# PFC_v1.net
KiCad netlist of a schematic drawn in EAGLE
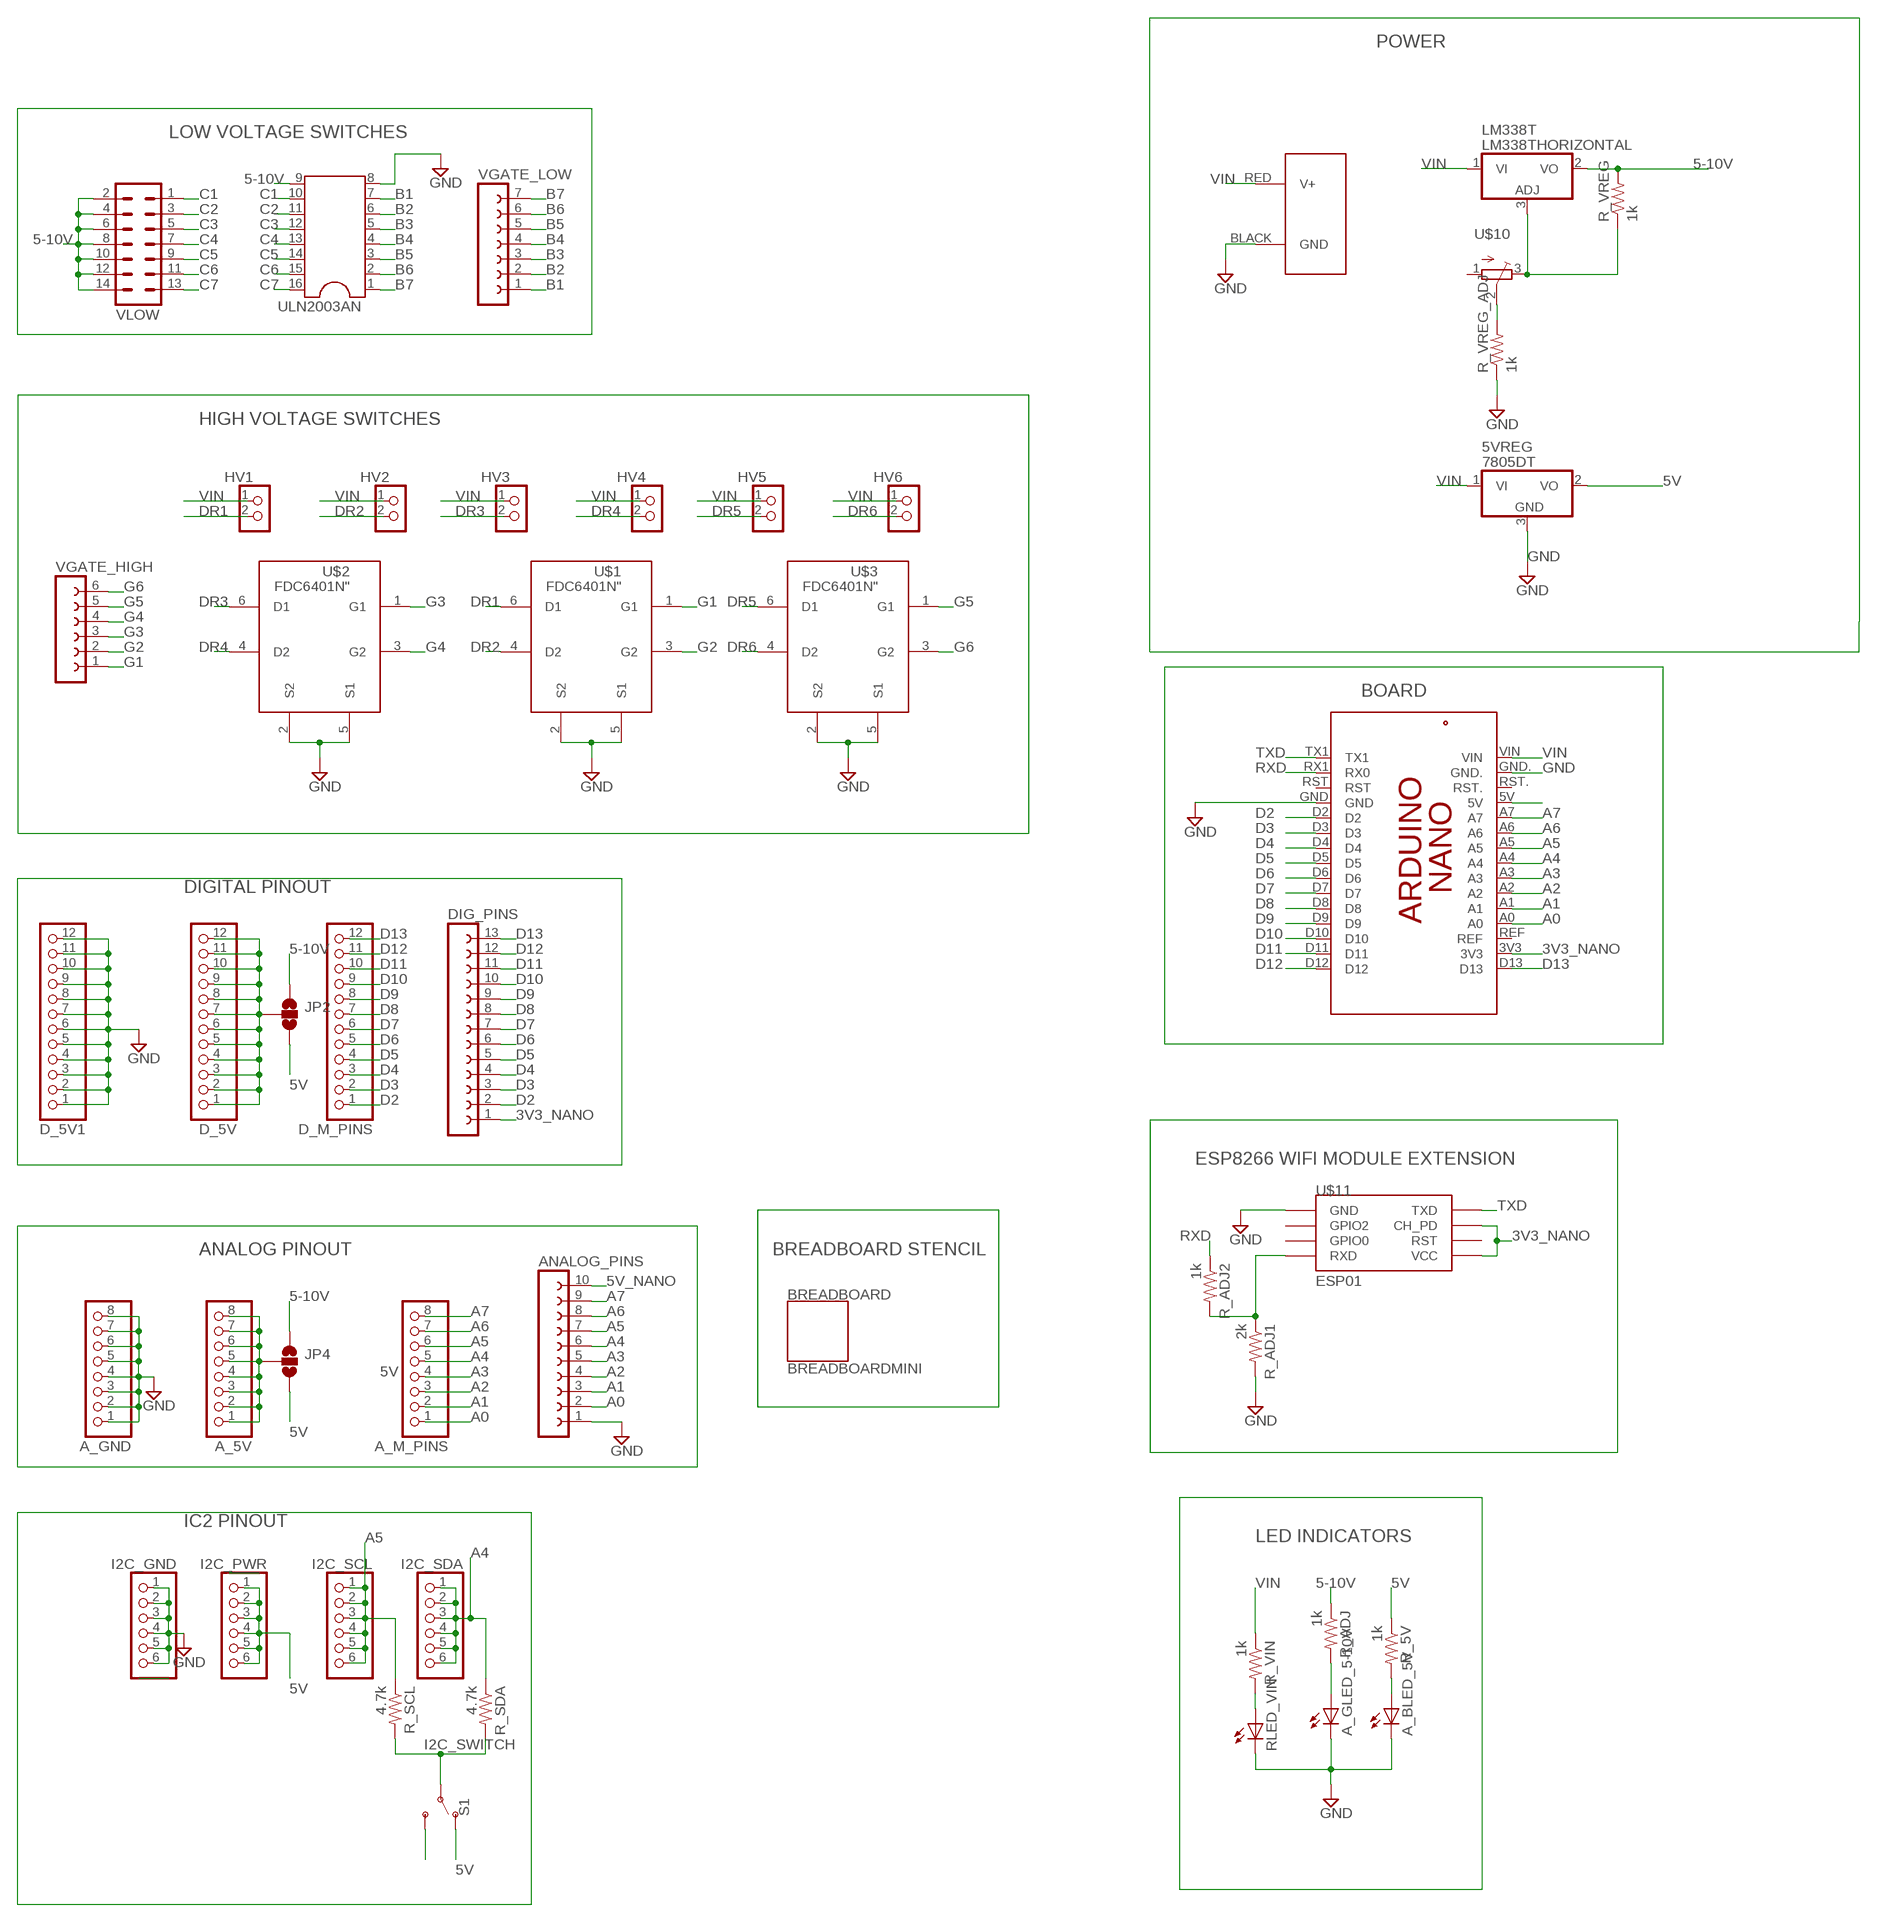
[diagram p0: schematic, sheet 1]

(export (version "E")
  (design (tool "Eeschema 10.0.6"))
  (components
    (comp (ref "5VREG")
      (value "7805DT")
      (footprint "eagle-import:TO252")
      (libsource (lib "eagle-import") (part "78DT05"))
    )
    (comp (ref "ANALOG_PINS")
      (value "FE10-1")
      (footprint "eagle-import:FE10")
      (libsource (lib "eagle-import") (part "FE10-1"))
    )
    (comp (ref "A_5V")
      (value "PINHD-1X8CLEANBIG")
      (footprint "eagle-import:1X08-CLEANBIG")
      (libsource (lib "eagle-import") (part "PINHD-1X8CLEANBIG"))
    )
    (comp (ref "A_BLED_5V")
      (value "LEDCHIP-LED0603")
      (footprint "eagle-import:CHIP-LED0603")
      (libsource (lib "eagle-import") (part "LEDCHIP-LED0603"))
    )
    (comp (ref "A_GLED_5-10V")
      (value "LEDCHIP-LED0603")
      (footprint "eagle-import:CHIP-LED0603")
      (libsource (lib "eagle-import") (part "LEDCHIP-LED0603"))
    )
    (comp (ref "A_GND")
      (value "PINHD-1X8CLEANBIG")
      (footprint "eagle-import:1X08-CLEANBIG")
      (libsource (lib "eagle-import") (part "PINHD-1X8CLEANBIG"))
    )
    (comp (ref "A_M_PINS")
      (value "PINHD-1X8CLEANBIG")
      (footprint "eagle-import:1X08-CLEANBIG")
      (libsource (lib "eagle-import") (part "PINHD-1X8CLEANBIG"))
    )
    (comp (ref "BREADBOARD")
      (value "BREADBOARDMINI")
      (footprint "eagle-import:BREADBOARD-MINI")
      (libsource (lib "eagle-import") (part "BREADBOARDMINI"))
    )
    (comp (ref "DIG_PINS")
      (value "FE13-1")
      (footprint "eagle-import:FE13")
      (libsource (lib "eagle-import") (part "FE13-1"))
    )
    (comp (ref "D_5V")
      (value "PINHD-1X12-CB")
      (footprint "eagle-import:1X12-CB")
      (libsource (lib "eagle-import") (part "PINHD-1X12-CB"))
    )
    (comp (ref "D_5V1")
      (value "PINHD-1X12-CB")
      (footprint "eagle-import:1X12-CB")
      (libsource (lib "eagle-import") (part "PINHD-1X12-CB"))
    )
    (comp (ref "D_M_PINS")
      (value "PINHD-1X12-CB")
      (footprint "eagle-import:1X12-CB")
      (libsource (lib "eagle-import") (part "PINHD-1X12-CB"))
    )
    (comp (ref "HV1")
      (value "PINHD-2X1")
      (footprint "eagle-import:2X01")
      (libsource (lib "eagle-import") (part "PINHD-2X1"))
    )
    (comp (ref "HV2")
      (value "PINHD-2X1")
      (footprint "eagle-import:2X01")
      (libsource (lib "eagle-import") (part "PINHD-2X1"))
    )
    (comp (ref "HV3")
      (value "PINHD-2X1")
      (footprint "eagle-import:2X01")
      (libsource (lib "eagle-import") (part "PINHD-2X1"))
    )
    (comp (ref "HV4")
      (value "PINHD-2X1")
      (footprint "eagle-import:2X01")
      (libsource (lib "eagle-import") (part "PINHD-2X1"))
    )
    (comp (ref "HV5")
      (value "PINHD-2X1")
      (footprint "eagle-import:2X01")
      (libsource (lib "eagle-import") (part "PINHD-2X1"))
    )
    (comp (ref "HV6")
      (value "PINHD-2X1")
      (footprint "eagle-import:2X01")
      (libsource (lib "eagle-import") (part "PINHD-2X1"))
    )
    (comp (ref "I2C_GND")
      (value "PINHD-1X6CLEAN")
      (footprint "eagle-import:1X06-CLEAN")
      (libsource (lib "eagle-import") (part "PINHD-1X6CLEAN"))
    )
    (comp (ref "I2C_PWR")
      (value "PINHD-1X6CLEAN")
      (footprint "eagle-import:1X06-CLEAN")
      (libsource (lib "eagle-import") (part "PINHD-1X6CLEAN"))
    )
    (comp (ref "I2C_SCL")
      (value "PINHD-1X6CLEAN")
      (footprint "eagle-import:1X06-CLEAN")
      (libsource (lib "eagle-import") (part "PINHD-1X6CLEAN"))
    )
    (comp (ref "I2C_SDA")
      (value "PINHD-1X6CLEAN")
      (footprint "eagle-import:1X06-CLEAN")
      (libsource (lib "eagle-import") (part "PINHD-1X6CLEAN"))
    )
    (comp (ref "J1")
      (value "POWERPOLE_POWER25A_HORIZONTAL_G2")
      (footprint "eagle-import:POWERPOLE_PAIR_25A_HORIZ_G2")
      (libsource (lib "eagle-import") (part "POWERPOLE_POWER25A_HORIZONTAL_G2"))
    )
    (comp (ref "JP2")
      (value "SOLDERJUMPER_2WAYT")
      (footprint "eagle-import:SJ_2")
      (libsource (lib "eagle-import") (part "SOLDERJUMPER_2WAYT"))
    )
    (comp (ref "JP4")
      (value "SOLDERJUMPER_2WAYT")
      (footprint "eagle-import:SJ_2")
      (libsource (lib "eagle-import") (part "SOLDERJUMPER_2WAYT"))
    )
    (comp (ref "LM338T")
      (value "LM338THORIZONTAL")
      (footprint "eagle-import:TO220H")
      (libsource (lib "eagle-import") (part "LM338THORIZONTAL"))
    )
    (comp (ref "PCB1")
      (value "ARDUINO_NANO_SHIELD")
      (footprint "eagle-import:ARDUINO_NANO_SHIELD")
      (libsource (lib "eagle-import") (part "ARDUINO_NANO_SHIELD"))
    )
    (comp (ref "RLED_VIN")
      (value "LEDCHIP-LED0603")
      (footprint "eagle-import:CHIP-LED0603")
      (libsource (lib "eagle-import") (part "LEDCHIP-LED0603"))
    )
    (comp (ref "R_5V")
      (value "1k")
      (footprint "eagle-import:R0603")
      (libsource (lib "eagle-import") (part "R-US_R0603"))
    )
    (comp (ref "R_ADJ")
      (value "1k")
      (footprint "eagle-import:R0603")
      (libsource (lib "eagle-import") (part "R-US_R0603"))
    )
    (comp (ref "R_ADJ1")
      (value "2k")
      (footprint "eagle-import:R0603")
      (libsource (lib "eagle-import") (part "R-US_R0603"))
    )
    (comp (ref "R_ADJ2")
      (value "1k")
      (footprint "eagle-import:R0603")
      (libsource (lib "eagle-import") (part "R-US_R0603"))
    )
    (comp (ref "R_SCL")
      (value "4.7k")
      (footprint "eagle-import:R0603")
      (libsource (lib "eagle-import") (part "R-US_R0603"))
    )
    (comp (ref "R_SDA")
      (value "4.7k")
      (footprint "eagle-import:R0603")
      (libsource (lib "eagle-import") (part "R-US_R0603"))
    )
    (comp (ref "R_VIN")
      (value "1k")
      (footprint "eagle-import:R0603")
      (libsource (lib "eagle-import") (part "R-US_R0603"))
    )
    (comp (ref "R_VREG")
      (value "1k")
      (footprint "eagle-import:R0603")
      (libsource (lib "eagle-import") (part "R-US_R0603"))
    )
    (comp (ref "R_VREG_ADJ")
      (value "1k")
      (footprint "eagle-import:R0603")
      (libsource (lib "eagle-import") (part "R-US_R0603"))
    )
    (comp (ref "S1")
      (value "SWITCH-SPDT-PTH-11.6X4.0MM")
      (footprint "eagle-import:SWITCH_SPDT_PTH_11.6X4.0MM")
      (libsource (lib "eagle-import") (part "SWITCH-SPDT-PTH-11.6X4.0MM"))
    )
    (comp (ref "U$1")
      (value "FDC6401N\"")
      (footprint "eagle-import:SSOT-6")
      (libsource (lib "eagle-import") (part "FDC6401N{dblquote}"))
    )
    (comp (ref "U$2")
      (value "FDC6401N\"")
      (footprint "eagle-import:SSOT-6")
      (libsource (lib "eagle-import") (part "FDC6401N{dblquote}"))
    )
    (comp (ref "U$3")
      (value "FDC6401N\"")
      (footprint "eagle-import:SSOT-6")
      (libsource (lib "eagle-import") (part "FDC6401N{dblquote}"))
    )
    (comp (ref "U$10")
      (value "TRIMPOTTC33X")
      (footprint "eagle-import:TC33X")
      (libsource (lib "eagle-import") (part "TRIMPOTTC33X"))
    )
    (comp (ref "U$11")
      (value "ESP01")
      (footprint "eagle-import:ESP01")
      (libsource (lib "eagle-import") (part "ESP01"))
    )
    (comp (ref "ULN2003AN")
      (value "DIL16S")
      (footprint "eagle-import:SOCKET-16")
      (libsource (lib "eagle-import") (part "DIL16S"))
    )
    (comp (ref "VGATE_HIGH")
      (value "FE06-1")
      (footprint "eagle-import:FE06")
      (libsource (lib "eagle-import") (part "FE06-1"))
    )
    (comp (ref "VGATE_LOW")
      (value "FE07-1")
      (footprint "eagle-import:FE07")
      (libsource (lib "eagle-import") (part "FE07-1"))
    )
    (comp (ref "VLOW")
      (value "MA07-2")
      (footprint "eagle-import:MA07-2")
      (libsource (lib "eagle-import") (part "MA07-2"))
    )
  )
  (nets
    (net (code "1") (name "/3V3_NANO") (class "Default")
      (node (ref "DIG_PINS") (pin "1") (pinfunction "1_1") (pintype "passive"))
      (node (ref "PCB1") (pin "3V3") (pinfunction "3V3_3V3") (pintype "bidirectional"))
      (node (ref "U$11") (pin "CH_PD") (pinfunction "CH_PD_CH_PD") (pintype "bidirectional"))
      (node (ref "U$11") (pin "VCC") (pinfunction "VCC_VCC") (pintype "bidirectional"))
    )
    (net (code "2") (name "/5-10V") (class "Default")
      (node (ref "JP2") (pin "1") (pinfunction "1_1") (pintype "passive"))
      (node (ref "JP4") (pin "1") (pinfunction "1_1") (pintype "passive"))
      (node (ref "LM338T") (pin "2") (pinfunction "VO_2") (pintype "passive"))
      (node (ref "R_ADJ") (pin "1") (pinfunction "1_1") (pintype "passive"))
      (node (ref "R_VREG") (pin "2") (pinfunction "2_2") (pintype "passive"))
      (node (ref "ULN2003AN") (pin "9") (pinfunction "9_9") (pintype "passive"))
      (node (ref "VLOW") (pin "10") (pinfunction "10_10") (pintype "passive"))
      (node (ref "VLOW") (pin "12") (pinfunction "12_12") (pintype "passive"))
      (node (ref "VLOW") (pin "14") (pinfunction "14_14") (pintype "passive"))
      (node (ref "VLOW") (pin "2") (pinfunction "2_2") (pintype "passive"))
      (node (ref "VLOW") (pin "4") (pinfunction "4_4") (pintype "passive"))
      (node (ref "VLOW") (pin "6") (pinfunction "6_6") (pintype "passive"))
      (node (ref "VLOW") (pin "8") (pinfunction "8_8") (pintype "passive"))
    )
    (net (code "3") (name "/5V") (class "Default")
      (node (ref "5VREG") (pin "2") (pinfunction "VO_2") (pintype "passive"))
      (node (ref "I2C_PWR") (pin "1") (pinfunction "1_1") (pintype "passive"))
      (node (ref "I2C_PWR") (pin "2") (pinfunction "2_2") (pintype "passive"))
      (node (ref "I2C_PWR") (pin "3") (pinfunction "3_3") (pintype "passive"))
      (node (ref "I2C_PWR") (pin "4") (pinfunction "4_4") (pintype "passive"))
      (node (ref "I2C_PWR") (pin "5") (pinfunction "5_5") (pintype "passive"))
      (node (ref "I2C_PWR") (pin "6") (pinfunction "6_6") (pintype "passive"))
      (node (ref "JP2") (pin "3") (pinfunction "3_3") (pintype "passive"))
      (node (ref "JP4") (pin "3") (pinfunction "3_3") (pintype "passive"))
      (node (ref "R_5V") (pin "1") (pinfunction "1_1") (pintype "passive"))
      (node (ref "S1") (pin "1") (pinfunction "O_1") (pintype "passive"))
    )
    (net (code "4") (name "/5V_NANO") (class "Default")
      (node (ref "ANALOG_PINS") (pin "10") (pinfunction "10_10") (pintype "passive"))
      (node (ref "PCB1") (pin "5V") (pinfunction "5V_5V") (pintype "bidirectional"))
    )
    (net (code "5") (name "/A0") (class "Default")
      (node (ref "ANALOG_PINS") (pin "2") (pinfunction "2_2") (pintype "passive"))
      (node (ref "A_M_PINS") (pin "1") (pinfunction "1_1") (pintype "passive"))
      (node (ref "PCB1") (pin "A0") (pinfunction "A0_A0") (pintype "bidirectional"))
    )
    (net (code "6") (name "/A1") (class "Default")
      (node (ref "ANALOG_PINS") (pin "3") (pinfunction "3_3") (pintype "passive"))
      (node (ref "A_M_PINS") (pin "2") (pinfunction "2_2") (pintype "passive"))
      (node (ref "PCB1") (pin "A1") (pinfunction "A1_A1") (pintype "bidirectional"))
    )
    (net (code "7") (name "/A2") (class "Default")
      (node (ref "ANALOG_PINS") (pin "4") (pinfunction "4_4") (pintype "passive"))
      (node (ref "A_M_PINS") (pin "3") (pinfunction "3_3") (pintype "passive"))
      (node (ref "PCB1") (pin "A2") (pinfunction "A2_A2") (pintype "bidirectional"))
    )
    (net (code "8") (name "/A3") (class "Default")
      (node (ref "ANALOG_PINS") (pin "5") (pinfunction "5_5") (pintype "passive"))
      (node (ref "A_M_PINS") (pin "4") (pinfunction "4_4") (pintype "passive"))
      (node (ref "PCB1") (pin "A3") (pinfunction "A3_A3") (pintype "bidirectional"))
    )
    (net (code "9") (name "/A4") (class "Default")
      (node (ref "ANALOG_PINS") (pin "6") (pinfunction "6_6") (pintype "passive"))
      (node (ref "A_M_PINS") (pin "5") (pinfunction "5_5") (pintype "passive"))
      (node (ref "I2C_SDA") (pin "1") (pinfunction "1_1") (pintype "passive"))
      (node (ref "I2C_SDA") (pin "2") (pinfunction "2_2") (pintype "passive"))
      (node (ref "I2C_SDA") (pin "3") (pinfunction "3_3") (pintype "passive"))
      (node (ref "I2C_SDA") (pin "4") (pinfunction "4_4") (pintype "passive"))
      (node (ref "I2C_SDA") (pin "5") (pinfunction "5_5") (pintype "passive"))
      (node (ref "I2C_SDA") (pin "6") (pinfunction "6_6") (pintype "passive"))
      (node (ref "PCB1") (pin "A4") (pinfunction "A4_A4") (pintype "bidirectional"))
      (node (ref "R_SDA") (pin "1") (pinfunction "1_1") (pintype "passive"))
    )
    (net (code "10") (name "/A5") (class "Default")
      (node (ref "ANALOG_PINS") (pin "7") (pinfunction "7_7") (pintype "passive"))
      (node (ref "A_M_PINS") (pin "6") (pinfunction "6_6") (pintype "passive"))
      (node (ref "I2C_SCL") (pin "1") (pinfunction "1_1") (pintype "passive"))
      (node (ref "I2C_SCL") (pin "2") (pinfunction "2_2") (pintype "passive"))
      (node (ref "I2C_SCL") (pin "3") (pinfunction "3_3") (pintype "passive"))
      (node (ref "I2C_SCL") (pin "4") (pinfunction "4_4") (pintype "passive"))
      (node (ref "I2C_SCL") (pin "5") (pinfunction "5_5") (pintype "passive"))
      (node (ref "I2C_SCL") (pin "6") (pinfunction "6_6") (pintype "passive"))
      (node (ref "PCB1") (pin "A5") (pinfunction "A5_A5") (pintype "bidirectional"))
      (node (ref "R_SCL") (pin "1") (pinfunction "1_1") (pintype "passive"))
    )
    (net (code "11") (name "/A6") (class "Default")
      (node (ref "ANALOG_PINS") (pin "8") (pinfunction "8_8") (pintype "passive"))
      (node (ref "A_M_PINS") (pin "7") (pinfunction "7_7") (pintype "passive"))
      (node (ref "PCB1") (pin "A6") (pinfunction "A6_A6") (pintype "bidirectional"))
    )
    (net (code "12") (name "/A7") (class "Default")
      (node (ref "ANALOG_PINS") (pin "9") (pinfunction "9_9") (pintype "passive"))
      (node (ref "A_M_PINS") (pin "8") (pinfunction "8_8") (pintype "passive"))
      (node (ref "PCB1") (pin "A7") (pinfunction "A7_A7") (pintype "bidirectional"))
    )
    (net (code "13") (name "/B1") (class "Default")
      (node (ref "ULN2003AN") (pin "7") (pinfunction "7_7") (pintype "passive"))
      (node (ref "VGATE_LOW") (pin "1") (pinfunction "1_1") (pintype "passive"))
    )
    (net (code "14") (name "/B2") (class "Default")
      (node (ref "ULN2003AN") (pin "6") (pinfunction "6_6") (pintype "passive"))
      (node (ref "VGATE_LOW") (pin "2") (pinfunction "2_2") (pintype "passive"))
    )
    (net (code "15") (name "/B3") (class "Default")
      (node (ref "ULN2003AN") (pin "5") (pinfunction "5_5") (pintype "passive"))
      (node (ref "VGATE_LOW") (pin "3") (pinfunction "3_3") (pintype "passive"))
    )
    (net (code "16") (name "/B4") (class "Default")
      (node (ref "ULN2003AN") (pin "4") (pinfunction "4_4") (pintype "passive"))
      (node (ref "VGATE_LOW") (pin "4") (pinfunction "4_4") (pintype "passive"))
    )
    (net (code "17") (name "/B5") (class "Default")
      (node (ref "ULN2003AN") (pin "3") (pinfunction "3_3") (pintype "passive"))
      (node (ref "VGATE_LOW") (pin "5") (pinfunction "5_5") (pintype "passive"))
    )
    (net (code "18") (name "/B6") (class "Default")
      (node (ref "ULN2003AN") (pin "2") (pinfunction "2_2") (pintype "passive"))
      (node (ref "VGATE_LOW") (pin "6") (pinfunction "6_6") (pintype "passive"))
    )
    (net (code "19") (name "/B7") (class "Default")
      (node (ref "ULN2003AN") (pin "1") (pinfunction "1_1") (pintype "passive"))
      (node (ref "VGATE_LOW") (pin "7") (pinfunction "7_7") (pintype "passive"))
    )
    (net (code "20") (name "/C1") (class "Default")
      (node (ref "ULN2003AN") (pin "10") (pinfunction "10_10") (pintype "passive"))
      (node (ref "VLOW") (pin "1") (pinfunction "1_1") (pintype "passive"))
    )
    (net (code "21") (name "/C2") (class "Default")
      (node (ref "ULN2003AN") (pin "11") (pinfunction "11_11") (pintype "passive"))
      (node (ref "VLOW") (pin "3") (pinfunction "3_3") (pintype "passive"))
    )
    (net (code "22") (name "/C3") (class "Default")
      (node (ref "ULN2003AN") (pin "12") (pinfunction "12_12") (pintype "passive"))
      (node (ref "VLOW") (pin "5") (pinfunction "5_5") (pintype "passive"))
    )
    (net (code "23") (name "/C4") (class "Default")
      (node (ref "ULN2003AN") (pin "13") (pinfunction "13_13") (pintype "passive"))
      (node (ref "VLOW") (pin "7") (pinfunction "7_7") (pintype "passive"))
    )
    (net (code "24") (name "/C5") (class "Default")
      (node (ref "ULN2003AN") (pin "14") (pinfunction "14_14") (pintype "passive"))
      (node (ref "VLOW") (pin "9") (pinfunction "9_9") (pintype "passive"))
    )
    (net (code "25") (name "/C6") (class "Default")
      (node (ref "ULN2003AN") (pin "15") (pinfunction "15_15") (pintype "passive"))
      (node (ref "VLOW") (pin "11") (pinfunction "11_11") (pintype "passive"))
    )
    (net (code "26") (name "/C7") (class "Default")
      (node (ref "ULN2003AN") (pin "16") (pinfunction "16_16") (pintype "passive"))
      (node (ref "VLOW") (pin "13") (pinfunction "13_13") (pintype "passive"))
    )
    (net (code "27") (name "/D2") (class "Default")
      (node (ref "DIG_PINS") (pin "2") (pinfunction "2_2") (pintype "passive"))
      (node (ref "D_M_PINS") (pin "1") (pinfunction "1_1") (pintype "passive"))
      (node (ref "PCB1") (pin "D2") (pinfunction "D2_D2") (pintype "bidirectional"))
    )
    (net (code "28") (name "/D3") (class "Default")
      (node (ref "DIG_PINS") (pin "3") (pinfunction "3_3") (pintype "passive"))
      (node (ref "D_M_PINS") (pin "2") (pinfunction "2_2") (pintype "passive"))
      (node (ref "PCB1") (pin "D3") (pinfunction "D3_D3") (pintype "bidirectional"))
    )
    (net (code "29") (name "/D4") (class "Default")
      (node (ref "DIG_PINS") (pin "4") (pinfunction "4_4") (pintype "passive"))
      (node (ref "D_M_PINS") (pin "3") (pinfunction "3_3") (pintype "passive"))
      (node (ref "PCB1") (pin "D4") (pinfunction "D4_D4") (pintype "bidirectional"))
    )
    (net (code "30") (name "/D5") (class "Default")
      (node (ref "DIG_PINS") (pin "5") (pinfunction "5_5") (pintype "passive"))
      (node (ref "D_M_PINS") (pin "4") (pinfunction "4_4") (pintype "passive"))
      (node (ref "PCB1") (pin "D5") (pinfunction "D5_D5") (pintype "bidirectional"))
    )
    (net (code "31") (name "/D6") (class "Default")
      (node (ref "DIG_PINS") (pin "6") (pinfunction "6_6") (pintype "passive"))
      (node (ref "D_M_PINS") (pin "5") (pinfunction "5_5") (pintype "passive"))
      (node (ref "PCB1") (pin "D6") (pinfunction "D6_D6") (pintype "bidirectional"))
    )
    (net (code "32") (name "/D7") (class "Default")
      (node (ref "DIG_PINS") (pin "7") (pinfunction "7_7") (pintype "passive"))
      (node (ref "D_M_PINS") (pin "6") (pinfunction "6_6") (pintype "passive"))
      (node (ref "PCB1") (pin "D7") (pinfunction "D7_D7") (pintype "bidirectional"))
    )
    (net (code "33") (name "/D8") (class "Default")
      (node (ref "DIG_PINS") (pin "8") (pinfunction "8_8") (pintype "passive"))
      (node (ref "D_M_PINS") (pin "7") (pinfunction "7_7") (pintype "passive"))
      (node (ref "PCB1") (pin "D8") (pinfunction "D8_D8") (pintype "bidirectional"))
    )
    (net (code "34") (name "/D9") (class "Default")
      (node (ref "DIG_PINS") (pin "9") (pinfunction "9_9") (pintype "passive"))
      (node (ref "D_M_PINS") (pin "8") (pinfunction "8_8") (pintype "passive"))
      (node (ref "PCB1") (pin "D9") (pinfunction "D9_D9") (pintype "bidirectional"))
    )
    (net (code "35") (name "/D10") (class "Default")
      (node (ref "DIG_PINS") (pin "10") (pinfunction "10_10") (pintype "passive"))
      (node (ref "D_M_PINS") (pin "9") (pinfunction "9_9") (pintype "passive"))
      (node (ref "PCB1") (pin "D10") (pinfunction "D10_D10") (pintype "bidirectional"))
    )
    (net (code "36") (name "/D11") (class "Default")
      (node (ref "DIG_PINS") (pin "11") (pinfunction "11_11") (pintype "passive"))
      (node (ref "D_M_PINS") (pin "10") (pinfunction "10_10") (pintype "passive"))
      (node (ref "PCB1") (pin "D11") (pinfunction "D11_D11") (pintype "bidirectional"))
    )
    (net (code "37") (name "/D12") (class "Default")
      (node (ref "DIG_PINS") (pin "12") (pinfunction "12_12") (pintype "passive"))
      (node (ref "D_M_PINS") (pin "11") (pinfunction "11_11") (pintype "passive"))
      (node (ref "PCB1") (pin "D12") (pinfunction "D12_D12") (pintype "bidirectional"))
    )
    (net (code "38") (name "/D13") (class "Default")
      (node (ref "DIG_PINS") (pin "13") (pinfunction "13_13") (pintype "passive"))
      (node (ref "D_M_PINS") (pin "12") (pinfunction "12_12") (pintype "passive"))
      (node (ref "PCB1") (pin "D13") (pinfunction "D13_D13") (pintype "bidirectional"))
    )
    (net (code "39") (name "/DR1") (class "Default")
      (node (ref "HV1") (pin "2") (pinfunction "3_2") (pintype "passive"))
      (node (ref "U$1") (pin "6") (pinfunction "D1_6") (pintype "bidirectional"))
    )
    (net (code "40") (name "/DR2") (class "Default")
      (node (ref "HV2") (pin "2") (pinfunction "3_2") (pintype "passive"))
      (node (ref "U$1") (pin "4") (pinfunction "D2_4") (pintype "bidirectional"))
    )
    (net (code "41") (name "/DR3") (class "Default")
      (node (ref "HV3") (pin "2") (pinfunction "3_2") (pintype "passive"))
      (node (ref "U$2") (pin "6") (pinfunction "D1_6") (pintype "bidirectional"))
    )
    (net (code "42") (name "/DR4") (class "Default")
      (node (ref "HV4") (pin "2") (pinfunction "3_2") (pintype "passive"))
      (node (ref "U$2") (pin "4") (pinfunction "D2_4") (pintype "bidirectional"))
    )
    (net (code "43") (name "/DR5") (class "Default")
      (node (ref "HV5") (pin "2") (pinfunction "3_2") (pintype "passive"))
      (node (ref "U$3") (pin "6") (pinfunction "D1_6") (pintype "bidirectional"))
    )
    (net (code "44") (name "/DR6") (class "Default")
      (node (ref "HV6") (pin "2") (pinfunction "3_2") (pintype "passive"))
      (node (ref "U$3") (pin "4") (pinfunction "D2_4") (pintype "bidirectional"))
    )
    (net (code "45") (name "/G1") (class "Default")
      (node (ref "U$1") (pin "1") (pinfunction "G1_1") (pintype "bidirectional"))
      (node (ref "VGATE_HIGH") (pin "1") (pinfunction "1_1") (pintype "passive"))
    )
    (net (code "46") (name "/G2") (class "Default")
      (node (ref "U$1") (pin "3") (pinfunction "G2_3") (pintype "bidirectional"))
      (node (ref "VGATE_HIGH") (pin "2") (pinfunction "2_2") (pintype "passive"))
    )
    (net (code "47") (name "/G3") (class "Default")
      (node (ref "U$2") (pin "1") (pinfunction "G1_1") (pintype "bidirectional"))
      (node (ref "VGATE_HIGH") (pin "3") (pinfunction "3_3") (pintype "passive"))
    )
    (net (code "48") (name "/G4") (class "Default")
      (node (ref "U$2") (pin "3") (pinfunction "G2_3") (pintype "bidirectional"))
      (node (ref "VGATE_HIGH") (pin "4") (pinfunction "4_4") (pintype "passive"))
    )
    (net (code "49") (name "/G5") (class "Default")
      (node (ref "U$3") (pin "1") (pinfunction "G1_1") (pintype "bidirectional"))
      (node (ref "VGATE_HIGH") (pin "5") (pinfunction "5_5") (pintype "passive"))
    )
    (net (code "50") (name "/G6") (class "Default")
      (node (ref "U$3") (pin "3") (pinfunction "G2_3") (pintype "bidirectional"))
      (node (ref "VGATE_HIGH") (pin "6") (pinfunction "6_6") (pintype "passive"))
    )
    (net (code "51") (name "/I2C_SWITCH") (class "Default")
      (node (ref "R_SCL") (pin "2") (pinfunction "2_2") (pintype "passive"))
      (node (ref "R_SDA") (pin "2") (pinfunction "2_2") (pintype "passive"))
      (node (ref "S1") (pin "2") (pinfunction "P_2") (pintype "passive"))
    )
    (net (code "52") (name "/RXD") (class "Default")
      (node (ref "PCB1") (pin "RX1") (pinfunction "RX0_RX1") (pintype "bidirectional"))
      (node (ref "R_ADJ1") (pin "1") (pinfunction "1_1") (pintype "passive"))
      (node (ref "R_ADJ2") (pin "1") (pinfunction "1_1") (pintype "passive"))
      (node (ref "R_ADJ2") (pin "2") (pinfunction "2_2") (pintype "passive"))
      (node (ref "U$11") (pin "RX") (pinfunction "RXD_RX") (pintype "bidirectional"))
    )
    (net (code "53") (name "/TXD") (class "Default")
      (node (ref "PCB1") (pin "TX1") (pinfunction "TX1_TX1") (pintype "bidirectional"))
      (node (ref "U$11") (pin "TX") (pinfunction "TXD_TX") (pintype "bidirectional"))
    )
    (net (code "54") (name "/VIN") (class "Default")
      (node (ref "5VREG") (pin "1") (pinfunction "VI_1") (pintype "input"))
      (node (ref "HV1") (pin "1") (pinfunction "1_1") (pintype "passive"))
      (node (ref "HV2") (pin "1") (pinfunction "1_1") (pintype "passive"))
      (node (ref "HV3") (pin "1") (pinfunction "1_1") (pintype "passive"))
      (node (ref "HV4") (pin "1") (pinfunction "1_1") (pintype "passive"))
      (node (ref "HV5") (pin "1") (pinfunction "1_1") (pintype "passive"))
      (node (ref "HV6") (pin "1") (pinfunction "1_1") (pintype "passive"))
      (node (ref "J1") (pin "RED") (pinfunction "V+_RED") (pintype "power_in"))
      (node (ref "LM338T") (pin "1") (pinfunction "VI_1") (pintype "input"))
      (node (ref "PCB1") (pin "VIN") (pinfunction "VIN_VIN") (pintype "bidirectional"))
      (node (ref "R_VIN") (pin "1") (pinfunction "1_1") (pintype "passive"))
    )
    (net (code "55") (name "GND") (class "Default")
      (node (ref "5VREG") (pin "3") (pinfunction "GND_3") (pintype "passive"))
      (node (ref "ANALOG_PINS") (pin "1") (pinfunction "1_1") (pintype "passive"))
      (node (ref "A_BLED_5V") (pin "C") (pinfunction "C_C") (pintype "passive"))
      (node (ref "A_GLED_5-10V") (pin "C") (pinfunction "C_C") (pintype "passive"))
      (node (ref "A_GND") (pin "1") (pinfunction "1_1") (pintype "passive"))
      (node (ref "A_GND") (pin "2") (pinfunction "2_2") (pintype "passive"))
      (node (ref "A_GND") (pin "3") (pinfunction "3_3") (pintype "passive"))
      (node (ref "A_GND") (pin "4") (pinfunction "4_4") (pintype "passive"))
      (node (ref "A_GND") (pin "5") (pinfunction "5_5") (pintype "passive"))
      (node (ref "A_GND") (pin "6") (pinfunction "6_6") (pintype "passive"))
      (node (ref "A_GND") (pin "7") (pinfunction "7_7") (pintype "passive"))
      (node (ref "A_GND") (pin "8") (pinfunction "8_8") (pintype "passive"))
      (node (ref "D_5V1") (pin "1") (pinfunction "1_1") (pintype "passive"))
      (node (ref "D_5V1") (pin "10") (pinfunction "10_10") (pintype "passive"))
      (node (ref "D_5V1") (pin "11") (pinfunction "11_11") (pintype "passive"))
      (node (ref "D_5V1") (pin "12") (pinfunction "12_12") (pintype "passive"))
      (node (ref "D_5V1") (pin "2") (pinfunction "2_2") (pintype "passive"))
      (node (ref "D_5V1") (pin "3") (pinfunction "3_3") (pintype "passive"))
      (node (ref "D_5V1") (pin "4") (pinfunction "4_4") (pintype "passive"))
      (node (ref "D_5V1") (pin "5") (pinfunction "5_5") (pintype "passive"))
      (node (ref "D_5V1") (pin "6") (pinfunction "6_6") (pintype "passive"))
      (node (ref "D_5V1") (pin "7") (pinfunction "7_7") (pintype "passive"))
      (node (ref "D_5V1") (pin "8") (pinfunction "8_8") (pintype "passive"))
      (node (ref "D_5V1") (pin "9") (pinfunction "9_9") (pintype "passive"))
      (node (ref "I2C_GND") (pin "1") (pinfunction "1_1") (pintype "passive"))
      (node (ref "I2C_GND") (pin "2") (pinfunction "2_2") (pintype "passive"))
      (node (ref "I2C_GND") (pin "3") (pinfunction "3_3") (pintype "passive"))
      (node (ref "I2C_GND") (pin "4") (pinfunction "4_4") (pintype "passive"))
      (node (ref "I2C_GND") (pin "5") (pinfunction "5_5") (pintype "passive"))
      (node (ref "I2C_GND") (pin "6") (pinfunction "6_6") (pintype "passive"))
      (node (ref "J1") (pin "BLACK") (pinfunction "GND_BLACK") (pintype "power_in"))
      (node (ref "PCB1") (pin "GND") (pinfunction "GND_GND") (pintype "bidirectional"))
      (node (ref "PCB1") (pin "GND.") (pinfunction "GND._GND.") (pintype "bidirectional"))
      (node (ref "RLED_VIN") (pin "C") (pinfunction "C_C") (pintype "passive"))
      (node (ref "R_ADJ1") (pin "2") (pinfunction "2_2") (pintype "passive"))
      (node (ref "R_VREG_ADJ") (pin "1") (pinfunction "1_1") (pintype "passive"))
      (node (ref "U$1") (pin "2") (pinfunction "S2_2") (pintype "bidirectional"))
      (node (ref "U$1") (pin "5") (pinfunction "S1_5") (pintype "bidirectional"))
      (node (ref "U$11") (pin "GND") (pinfunction "GND_GND") (pintype "bidirectional"))
      (node (ref "U$2") (pin "2") (pinfunction "S2_2") (pintype "bidirectional"))
      (node (ref "U$2") (pin "5") (pinfunction "S1_5") (pintype "bidirectional"))
      (node (ref "U$3") (pin "2") (pinfunction "S2_2") (pintype "bidirectional"))
      (node (ref "U$3") (pin "5") (pinfunction "S1_5") (pintype "bidirectional"))
      (node (ref "ULN2003AN") (pin "8") (pinfunction "8_8") (pintype "passive"))
    )
    (net (code "56") (name "Net-(A_5V-Pad1)") (class "Default")
      (node (ref "A_5V") (pin "1") (pinfunction "1_1") (pintype "passive"))
      (node (ref "A_5V") (pin "2") (pinfunction "2_2") (pintype "passive"))
      (node (ref "A_5V") (pin "3") (pinfunction "3_3") (pintype "passive"))
      (node (ref "A_5V") (pin "4") (pinfunction "4_4") (pintype "passive"))
      (node (ref "A_5V") (pin "5") (pinfunction "5_5") (pintype "passive"))
      (node (ref "A_5V") (pin "6") (pinfunction "6_6") (pintype "passive"))
      (node (ref "A_5V") (pin "7") (pinfunction "7_7") (pintype "passive"))
      (node (ref "A_5V") (pin "8") (pinfunction "8_8") (pintype "passive"))
      (node (ref "JP4") (pin "2") (pinfunction "2_2") (pintype "passive"))
    )
    (net (code "57") (name "Net-(A_BLED_5V-PadA)") (class "Default")
      (node (ref "A_BLED_5V") (pin "A") (pinfunction "A_A") (pintype "passive"))
      (node (ref "R_5V") (pin "2") (pinfunction "2_2") (pintype "passive"))
    )
    (net (code "58") (name "Net-(A_GLED_5-10V-PadA)") (class "Default")
      (node (ref "A_GLED_5-10V") (pin "A") (pinfunction "A_A") (pintype "passive"))
      (node (ref "R_ADJ") (pin "2") (pinfunction "2_2") (pintype "passive"))
    )
    (net (code "59") (name "Net-(D_5V-Pad1)") (class "Default")
      (node (ref "D_5V") (pin "1") (pinfunction "1_1") (pintype "passive"))
      (node (ref "D_5V") (pin "10") (pinfunction "10_10") (pintype "passive"))
      (node (ref "D_5V") (pin "11") (pinfunction "11_11") (pintype "passive"))
      (node (ref "D_5V") (pin "12") (pinfunction "12_12") (pintype "passive"))
      (node (ref "D_5V") (pin "2") (pinfunction "2_2") (pintype "passive"))
      (node (ref "D_5V") (pin "3") (pinfunction "3_3") (pintype "passive"))
      (node (ref "D_5V") (pin "4") (pinfunction "4_4") (pintype "passive"))
      (node (ref "D_5V") (pin "5") (pinfunction "5_5") (pintype "passive"))
      (node (ref "D_5V") (pin "6") (pinfunction "6_6") (pintype "passive"))
      (node (ref "D_5V") (pin "7") (pinfunction "7_7") (pintype "passive"))
      (node (ref "D_5V") (pin "8") (pinfunction "8_8") (pintype "passive"))
      (node (ref "D_5V") (pin "9") (pinfunction "9_9") (pintype "passive"))
      (node (ref "JP2") (pin "2") (pinfunction "2_2") (pintype "passive"))
    )
    (net (code "60") (name "Net-(LM338T-GND)") (class "Default")
      (node (ref "LM338T") (pin "3") (pinfunction "GND_3") (pintype "passive"))
      (node (ref "R_VREG") (pin "1") (pinfunction "1_1") (pintype "passive"))
      (node (ref "U$10") (pin "3") (pinfunction "E_3") (pintype "passive"))
    )
    (net (code "61") (name "Net-(RLED_VIN-PadA)") (class "Default")
      (node (ref "RLED_VIN") (pin "A") (pinfunction "A_A") (pintype "passive"))
      (node (ref "R_VIN") (pin "2") (pinfunction "2_2") (pintype "passive"))
    )
    (net (code "62") (name "Net-(U$10-S)") (class "Default")
      (node (ref "R_VREG_ADJ") (pin "2") (pinfunction "2_2") (pintype "passive"))
      (node (ref "U$10") (pin "2") (pinfunction "S_2") (pintype "passive"))
    )
    (net (code "63") (name "unconnected-(PCB1-PadREF)") (class "Default")
      (node (ref "PCB1") (pin "REF") (pinfunction "REF_REF") (pintype "bidirectional"))
    )
    (net (code "64") (name "unconnected-(PCB1-PadRST)") (class "Default")
      (node (ref "PCB1") (pin "RST") (pinfunction "RST_RST") (pintype "bidirectional"))
    )
    (net (code "65") (name "unconnected-(PCB1-PadRST.)") (class "Default")
      (node (ref "PCB1") (pin "RST.") (pinfunction "RST._RST.") (pintype "bidirectional"))
    )
    (net (code "66") (name "unconnected-(S1-S-Pad3)") (class "Default")
      (node (ref "S1") (pin "3") (pinfunction "S_3") (pintype "passive"))
    )
    (net (code "67") (name "unconnected-(U$10-A-Pad1)") (class "Default")
      (node (ref "U$10") (pin "1") (pinfunction "A_1") (pintype "passive"))
    )
    (net (code "68") (name "unconnected-(U$11-PadGPIO0)") (class "Default")
      (node (ref "U$11") (pin "GPIO0") (pinfunction "GPIO0_GPIO0") (pintype "bidirectional"))
    )
    (net (code "69") (name "unconnected-(U$11-PadGPIO2)") (class "Default")
      (node (ref "U$11") (pin "GPIO2") (pinfunction "GPIO2_GPIO2") (pintype "bidirectional"))
    )
    (net (code "70") (name "unconnected-(U$11-PadRST)") (class "Default")
      (node (ref "U$11") (pin "RST") (pinfunction "RST_RST") (pintype "bidirectional"))
    )
  )
)
